# EasyEDA_SCH_Nanosec_Shifter_2022-09-27.net
KiCad netlist of a schematic drawn in EasyEDA
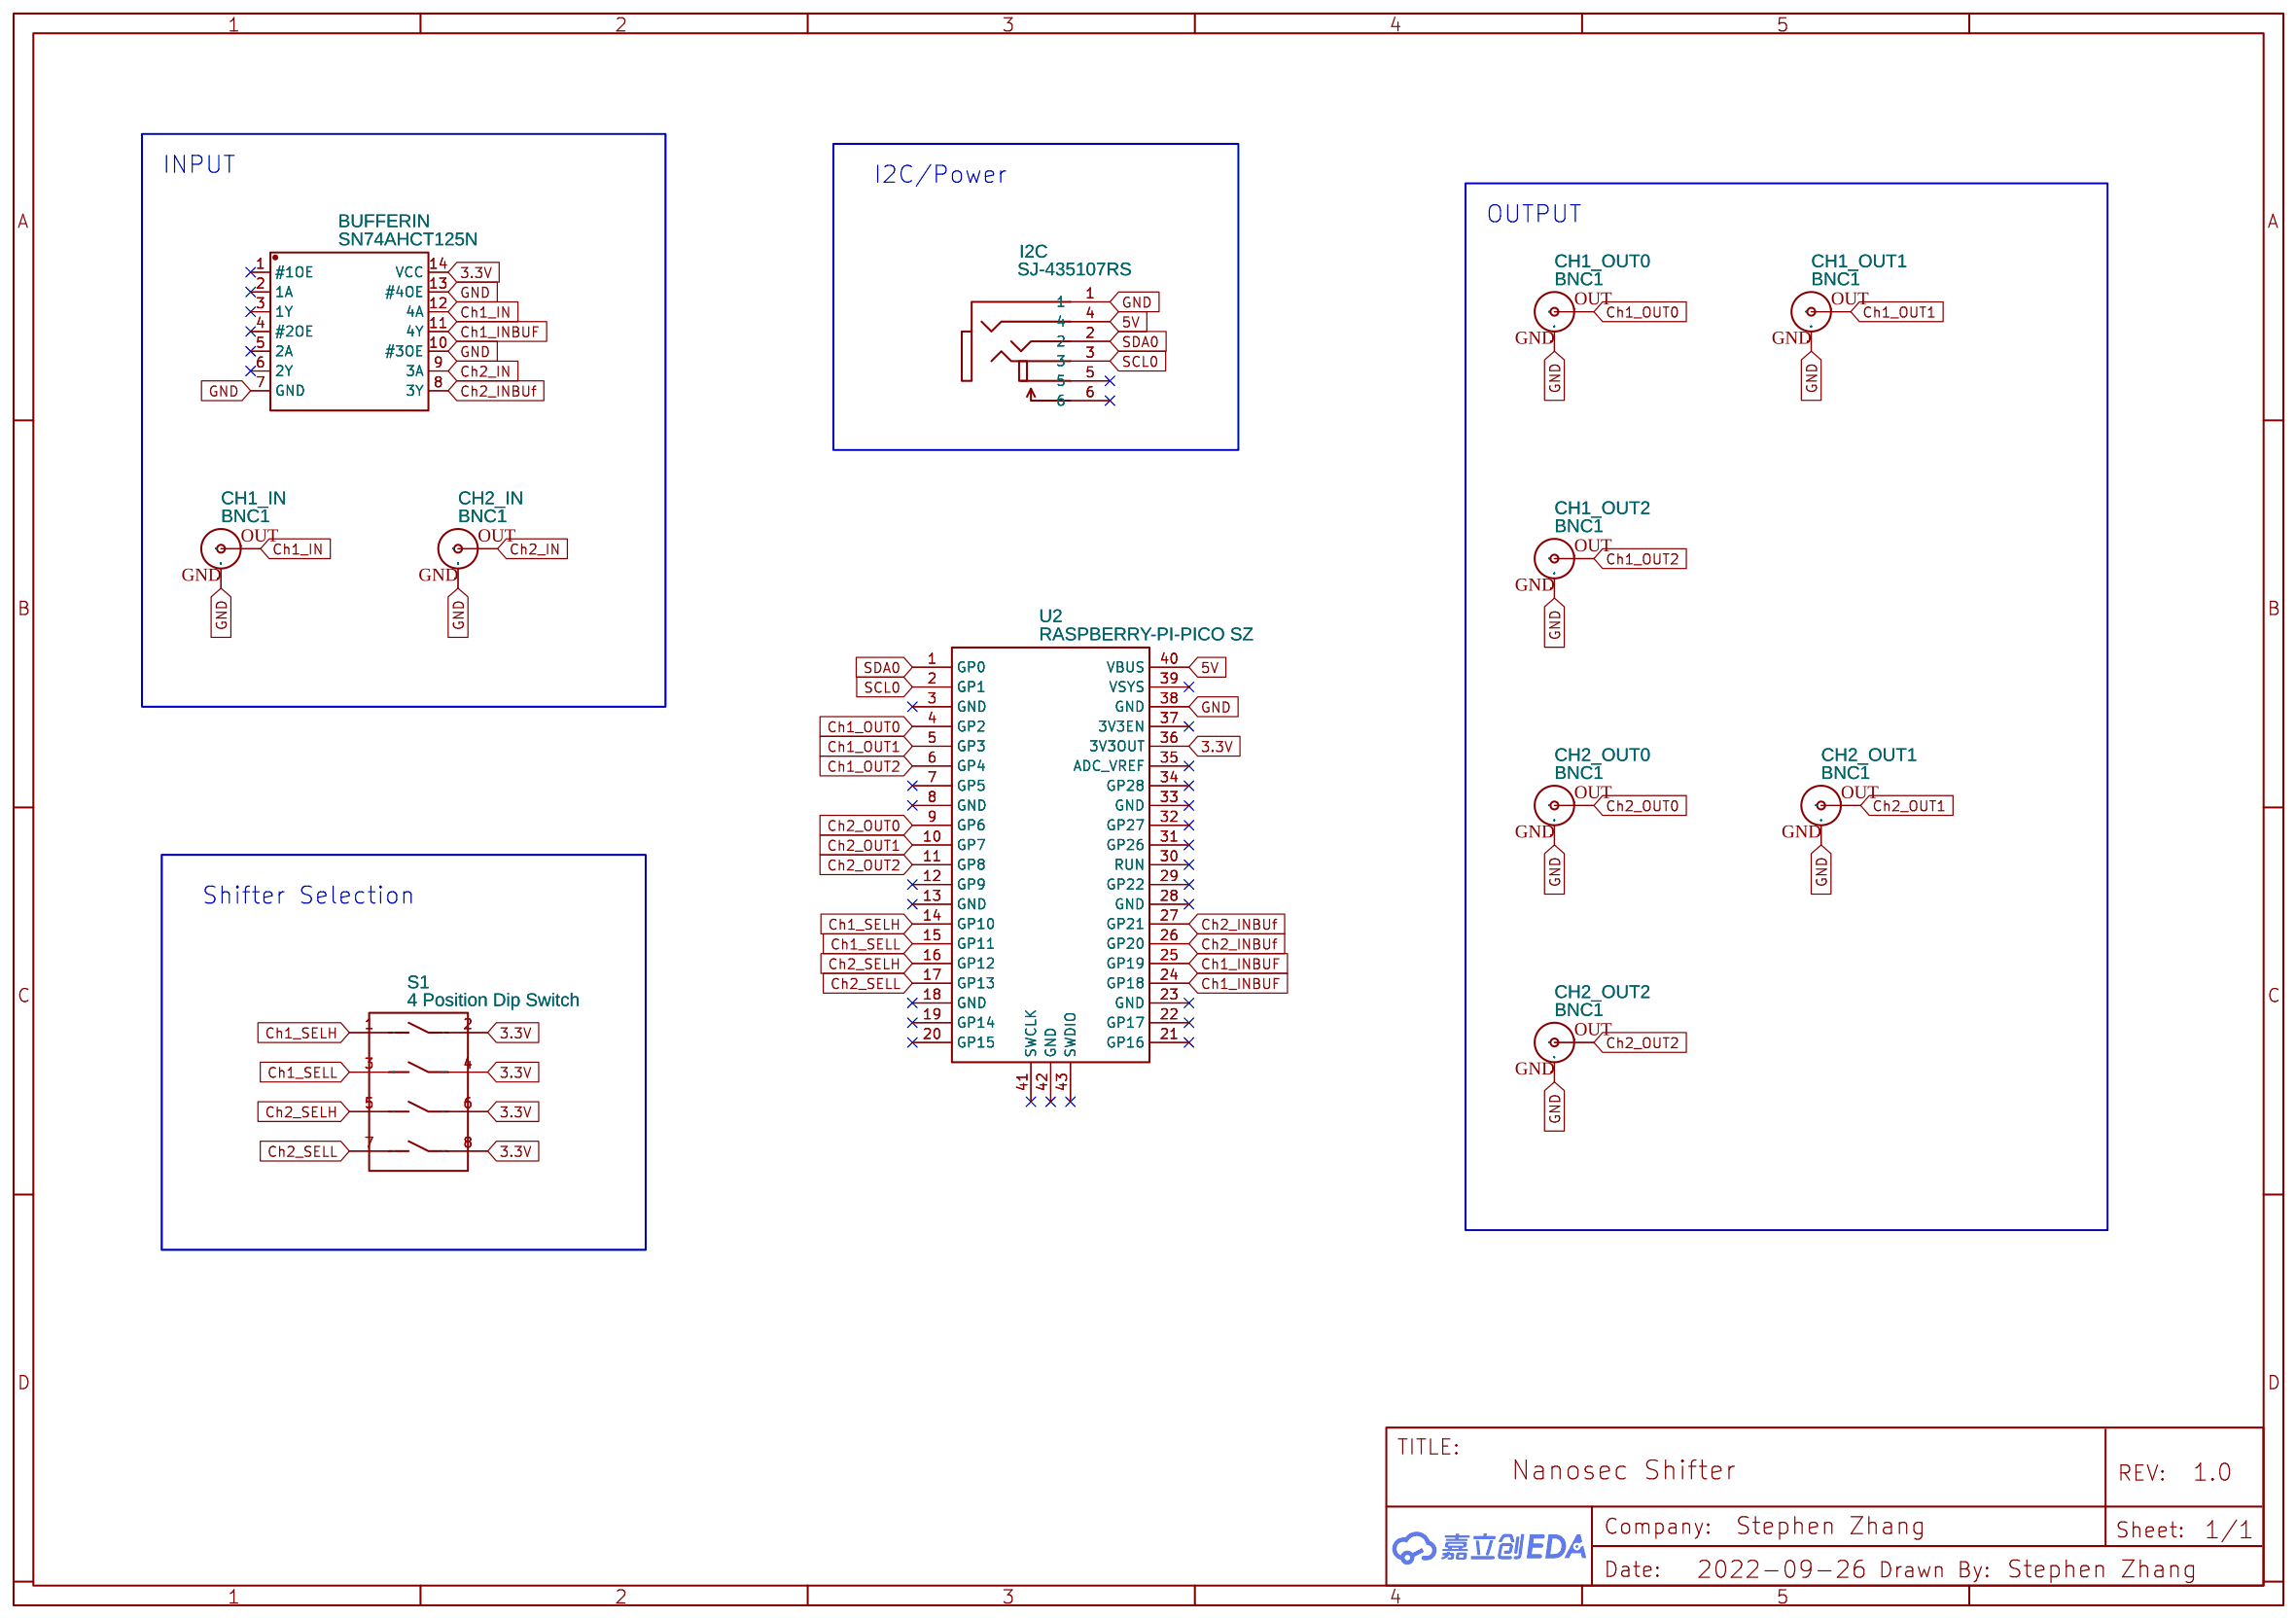
[diagram p0: schematic sheet]

(export (version "E")
  (design (tool "Eeschema 10.0.6"))
  (components
    (comp (ref "BUFFERIN")
      (value "SN74AHCT125N")
      (fields (field (name "BOM_Supplier Part") "C354152"))
      (libsource (lib "") (part "SN74AHCT125N"))
    )
    (comp (ref "CH1_IN") (value "BNC1") (libsource (lib "") (part "BNC1_2")))
    (comp (ref "CH1_OUT0") (value "BNC1") (libsource (lib "") (part "BNC1")))
    (comp (ref "CH1_OUT1") (value "BNC1") (libsource (lib "") (part "BNC1")))
    (comp (ref "CH1_OUT2") (value "BNC1") (libsource (lib "") (part "BNC1")))
    (comp (ref "CH2_IN") (value "BNC1") (libsource (lib "") (part "BNC1_3")))
    (comp (ref "CH2_OUT0") (value "BNC1") (libsource (lib "") (part "BNC1_1")))
    (comp (ref "CH2_OUT1") (value "BNC1") (libsource (lib "") (part "BNC1_1")))
    (comp (ref "CH2_OUT2") (value "BNC1") (libsource (lib "") (part "BNC1_1")))
    (comp (ref "I2C")
      (value "SJ-435107RS")
      (fields (field (name "BOM_Supplier Part") "490-SJ-435107RS"))
      (libsource (lib "") (part "SJ-435107RS"))
    )
    (comp (ref "S1")
      (value "4 Position Dip Switch")
      (fields (field (name "BOM_Manufacturer Part") "206-4LPST"))
      (libsource (lib "") (part "4 Position Dip Switch"))
    )
    (comp (ref "U2") (value "RASPBERRY-PI-PICO SZ") (libsource (lib "") (part "RASPBERRY-PI-PICO SZ")))
  )
  (nets
    (net (code "1") (name "3.3V") (class "Default")
      (node (ref "BUFFERIN") (pin "14") (pinfunction "VCC_14") (pintype "unspecified"))
      (node (ref "S1") (pin "2") (pinfunction "2_2") (pintype "unspecified"))
      (node (ref "S1") (pin "4") (pinfunction "4_4") (pintype "unspecified"))
      (node (ref "S1") (pin "6") (pinfunction "6_6") (pintype "unspecified"))
      (node (ref "S1") (pin "8") (pinfunction "8_8") (pintype "unspecified"))
      (node (ref "U2") (pin "36") (pinfunction "3V3OUT_36") (pintype "unspecified"))
    )
    (net (code "2") (name "5V") (class "Default")
      (node (ref "I2C") (pin "4") (pinfunction "4_4") (pintype "unspecified"))
      (node (ref "U2") (pin "40") (pinfunction "VBUS_40") (pintype "unspecified"))
    )
    (net (code "3") (name "Ch1_IN") (class "Default")
      (node (ref "BUFFERIN") (pin "12") (pinfunction "4A_12") (pintype "unspecified"))
      (node (ref "CH1_IN") (pin "S") (pinfunction "OUT_S") (pintype "unspecified"))
    )
    (net (code "4") (name "Ch1_INBUF") (class "Default")
      (node (ref "BUFFERIN") (pin "11") (pinfunction "4Y_11") (pintype "unspecified"))
      (node (ref "U2") (pin "24") (pinfunction "GP18_24") (pintype "unspecified"))
      (node (ref "U2") (pin "25") (pinfunction "GP19_25") (pintype "unspecified"))
    )
    (net (code "5") (name "Ch1_OUT0") (class "Default")
      (node (ref "CH1_OUT0") (pin "S") (pinfunction "OUT_S") (pintype "unspecified"))
      (node (ref "U2") (pin "4") (pinfunction "GP2_4") (pintype "unspecified"))
    )
    (net (code "6") (name "Ch1_OUT1") (class "Default")
      (node (ref "CH1_OUT1") (pin "S") (pinfunction "OUT_S") (pintype "unspecified"))
      (node (ref "U2") (pin "5") (pinfunction "GP3_5") (pintype "unspecified"))
    )
    (net (code "7") (name "Ch1_OUT2") (class "Default")
      (node (ref "CH1_OUT2") (pin "S") (pinfunction "OUT_S") (pintype "unspecified"))
      (node (ref "U2") (pin "6") (pinfunction "GP4_6") (pintype "unspecified"))
    )
    (net (code "8") (name "Ch1_SELH") (class "Default")
      (node (ref "S1") (pin "1") (pinfunction "1_1") (pintype "unspecified"))
      (node (ref "U2") (pin "14") (pinfunction "GP10_14") (pintype "unspecified"))
    )
    (net (code "9") (name "Ch1_SELL") (class "Default")
      (node (ref "S1") (pin "3") (pinfunction "3_3") (pintype "unspecified"))
      (node (ref "U2") (pin "15") (pinfunction "GP11_15") (pintype "unspecified"))
    )
    (net (code "10") (name "Ch2_IN") (class "Default")
      (node (ref "BUFFERIN") (pin "9") (pinfunction "3A_9") (pintype "unspecified"))
      (node (ref "CH2_IN") (pin "S") (pinfunction "OUT_S") (pintype "unspecified"))
    )
    (net (code "11") (name "Ch2_INBUf") (class "Default")
      (node (ref "BUFFERIN") (pin "8") (pinfunction "3Y_8") (pintype "unspecified"))
      (node (ref "U2") (pin "26") (pinfunction "GP20_26") (pintype "unspecified"))
      (node (ref "U2") (pin "27") (pinfunction "GP21_27") (pintype "unspecified"))
    )
    (net (code "12") (name "Ch2_OUT0") (class "Default")
      (node (ref "CH2_OUT0") (pin "S") (pinfunction "OUT_S") (pintype "unspecified"))
      (node (ref "U2") (pin "9") (pinfunction "GP6_9") (pintype "unspecified"))
    )
    (net (code "13") (name "Ch2_OUT1") (class "Default")
      (node (ref "CH2_OUT1") (pin "S") (pinfunction "OUT_S") (pintype "unspecified"))
      (node (ref "U2") (pin "10") (pinfunction "GP7_10") (pintype "unspecified"))
    )
    (net (code "14") (name "Ch2_OUT2") (class "Default")
      (node (ref "CH2_OUT2") (pin "S") (pinfunction "OUT_S") (pintype "unspecified"))
      (node (ref "U2") (pin "11") (pinfunction "GP8_11") (pintype "unspecified"))
    )
    (net (code "15") (name "Ch2_SELH") (class "Default")
      (node (ref "S1") (pin "5") (pinfunction "5_5") (pintype "unspecified"))
      (node (ref "U2") (pin "16") (pinfunction "GP12_16") (pintype "unspecified"))
    )
    (net (code "16") (name "Ch2_SELL") (class "Default")
      (node (ref "S1") (pin "7") (pinfunction "7_7") (pintype "unspecified"))
      (node (ref "U2") (pin "17") (pinfunction "GP13_17") (pintype "unspecified"))
    )
    (net (code "17") (name "GND") (class "Default")
      (node (ref "BUFFERIN") (pin "10") (pinfunction "#3OE_10") (pintype "unspecified"))
      (node (ref "BUFFERIN") (pin "13") (pinfunction "#4OE_13") (pintype "unspecified"))
      (node (ref "BUFFERIN") (pin "7") (pinfunction "GND_7") (pintype "unspecified"))
      (node (ref "CH1_IN") (pin "GND") (pinfunction "GND_GND") (pintype "unspecified"))
      (node (ref "CH1_OUT0") (pin "GND") (pinfunction "GND_GND") (pintype "unspecified"))
      (node (ref "CH1_OUT1") (pin "GND") (pinfunction "GND_GND") (pintype "unspecified"))
      (node (ref "CH1_OUT2") (pin "GND") (pinfunction "GND_GND") (pintype "unspecified"))
      (node (ref "CH2_IN") (pin "GND") (pinfunction "GND_GND") (pintype "unspecified"))
      (node (ref "CH2_OUT0") (pin "GND") (pinfunction "GND_GND") (pintype "unspecified"))
      (node (ref "CH2_OUT1") (pin "GND") (pinfunction "GND_GND") (pintype "unspecified"))
      (node (ref "CH2_OUT2") (pin "GND") (pinfunction "GND_GND") (pintype "unspecified"))
      (node (ref "I2C") (pin "1") (pinfunction "1_1") (pintype "unspecified"))
      (node (ref "U2") (pin "38") (pinfunction "GND_38") (pintype "unspecified"))
    )
    (net (code "18") (name "SCL0") (class "Default")
      (node (ref "I2C") (pin "3") (pinfunction "3_3") (pintype "unspecified"))
      (node (ref "U2") (pin "2") (pinfunction "GP1_2") (pintype "unspecified"))
    )
    (net (code "19") (name "SDA0") (class "Default")
      (node (ref "I2C") (pin "2") (pinfunction "2_2") (pintype "unspecified"))
      (node (ref "U2") (pin "1") (pinfunction "GP0_1") (pintype "unspecified"))
    )
    (net (code "20") (name "unconnected-(BUFFERIN-#1OE-Pad1)") (class "Default")
      (node (ref "BUFFERIN") (pin "1") (pinfunction "#1OE_1") (pintype "unspecified+no_connect"))
    )
    (net (code "21") (name "unconnected-(BUFFERIN-#2OE-Pad4)") (class "Default")
      (node (ref "BUFFERIN") (pin "4") (pinfunction "#2OE_4") (pintype "unspecified+no_connect"))
    )
    (net (code "22") (name "unconnected-(BUFFERIN-1A-Pad2)") (class "Default")
      (node (ref "BUFFERIN") (pin "2") (pinfunction "1A_2") (pintype "unspecified+no_connect"))
    )
    (net (code "23") (name "unconnected-(BUFFERIN-1Y-Pad3)") (class "Default")
      (node (ref "BUFFERIN") (pin "3") (pinfunction "1Y_3") (pintype "unspecified+no_connect"))
    )
    (net (code "24") (name "unconnected-(BUFFERIN-2A-Pad5)") (class "Default")
      (node (ref "BUFFERIN") (pin "5") (pinfunction "2A_5") (pintype "unspecified+no_connect"))
    )
    (net (code "25") (name "unconnected-(BUFFERIN-2Y-Pad6)") (class "Default")
      (node (ref "BUFFERIN") (pin "6") (pinfunction "2Y_6") (pintype "unspecified+no_connect"))
    )
    (net (code "26") (name "unconnected-(I2C-Pad5)") (class "Default")
      (node (ref "I2C") (pin "5") (pinfunction "5_5") (pintype "unspecified+no_connect"))
    )
    (net (code "27") (name "unconnected-(I2C-Pad6)") (class "Default")
      (node (ref "I2C") (pin "6") (pinfunction "6_6") (pintype "unspecified+no_connect"))
    )
    (net (code "28") (name "unconnected-(U2-3V3EN-Pad37)") (class "Default")
      (node (ref "U2") (pin "37") (pinfunction "3V3EN_37") (pintype "unspecified+no_connect"))
    )
    (net (code "29") (name "unconnected-(U2-ADC_VREF-Pad35)") (class "Default")
      (node (ref "U2") (pin "35") (pinfunction "ADC_VREF_35") (pintype "unspecified+no_connect"))
    )
    (net (code "30") (name "unconnected-(U2-GND-Pad3)") (class "Default")
      (node (ref "U2") (pin "3") (pinfunction "GND_3") (pintype "unspecified+no_connect"))
    )
    (net (code "31") (name "unconnected-(U2-GND-Pad8)") (class "Default")
      (node (ref "U2") (pin "8") (pinfunction "GND_8") (pintype "unspecified+no_connect"))
    )
    (net (code "32") (name "unconnected-(U2-GND-Pad13)") (class "Default")
      (node (ref "U2") (pin "13") (pinfunction "GND_13") (pintype "unspecified+no_connect"))
    )
    (net (code "33") (name "unconnected-(U2-GND-Pad18)") (class "Default")
      (node (ref "U2") (pin "18") (pinfunction "GND_18") (pintype "unspecified+no_connect"))
    )
    (net (code "34") (name "unconnected-(U2-GND-Pad23)") (class "Default")
      (node (ref "U2") (pin "23") (pinfunction "GND_23") (pintype "unspecified+no_connect"))
    )
    (net (code "35") (name "unconnected-(U2-GND-Pad28)") (class "Default")
      (node (ref "U2") (pin "28") (pinfunction "GND_28") (pintype "unspecified+no_connect"))
    )
    (net (code "36") (name "unconnected-(U2-GND-Pad33)") (class "Default")
      (node (ref "U2") (pin "33") (pinfunction "GND_33") (pintype "unspecified+no_connect"))
    )
    (net (code "37") (name "unconnected-(U2-GND-Pad42)") (class "Default")
      (node (ref "U2") (pin "42") (pinfunction "GND_42") (pintype "unspecified+no_connect"))
    )
    (net (code "38") (name "unconnected-(U2-GP5-Pad7)") (class "Default")
      (node (ref "U2") (pin "7") (pinfunction "GP5_7") (pintype "unspecified+no_connect"))
    )
    (net (code "39") (name "unconnected-(U2-GP9-Pad12)") (class "Default")
      (node (ref "U2") (pin "12") (pinfunction "GP9_12") (pintype "unspecified+no_connect"))
    )
    (net (code "40") (name "unconnected-(U2-GP14-Pad19)") (class "Default")
      (node (ref "U2") (pin "19") (pinfunction "GP14_19") (pintype "unspecified+no_connect"))
    )
    (net (code "41") (name "unconnected-(U2-GP15-Pad20)") (class "Default")
      (node (ref "U2") (pin "20") (pinfunction "GP15_20") (pintype "unspecified+no_connect"))
    )
    (net (code "42") (name "unconnected-(U2-GP16-Pad21)") (class "Default")
      (node (ref "U2") (pin "21") (pinfunction "GP16_21") (pintype "unspecified+no_connect"))
    )
    (net (code "43") (name "unconnected-(U2-GP17-Pad22)") (class "Default")
      (node (ref "U2") (pin "22") (pinfunction "GP17_22") (pintype "unspecified+no_connect"))
    )
    (net (code "44") (name "unconnected-(U2-GP22-Pad29)") (class "Default")
      (node (ref "U2") (pin "29") (pinfunction "GP22_29") (pintype "unspecified+no_connect"))
    )
    (net (code "45") (name "unconnected-(U2-GP26-Pad31)") (class "Default")
      (node (ref "U2") (pin "31") (pinfunction "GP26_31") (pintype "unspecified+no_connect"))
    )
    (net (code "46") (name "unconnected-(U2-GP27-Pad32)") (class "Default")
      (node (ref "U2") (pin "32") (pinfunction "GP27_32") (pintype "unspecified+no_connect"))
    )
    (net (code "47") (name "unconnected-(U2-GP28-Pad34)") (class "Default")
      (node (ref "U2") (pin "34") (pinfunction "GP28_34") (pintype "unspecified+no_connect"))
    )
    (net (code "48") (name "unconnected-(U2-RUN-Pad30)") (class "Default")
      (node (ref "U2") (pin "30") (pinfunction "RUN_30") (pintype "unspecified+no_connect"))
    )
    (net (code "49") (name "unconnected-(U2-SWCLK-Pad41)") (class "Default")
      (node (ref "U2") (pin "41") (pinfunction "SWCLK_41") (pintype "unspecified+no_connect"))
    )
    (net (code "50") (name "unconnected-(U2-SWDIO-Pad43)") (class "Default")
      (node (ref "U2") (pin "43") (pinfunction "SWDIO_43") (pintype "unspecified+no_connect"))
    )
    (net (code "51") (name "unconnected-(U2-VSYS-Pad39)") (class "Default")
      (node (ref "U2") (pin "39") (pinfunction "VSYS_39") (pintype "unspecified+no_connect"))
    )
  )
)
